# MAIN.net
KiCad netlist of a schematic drawn in Altium Designer
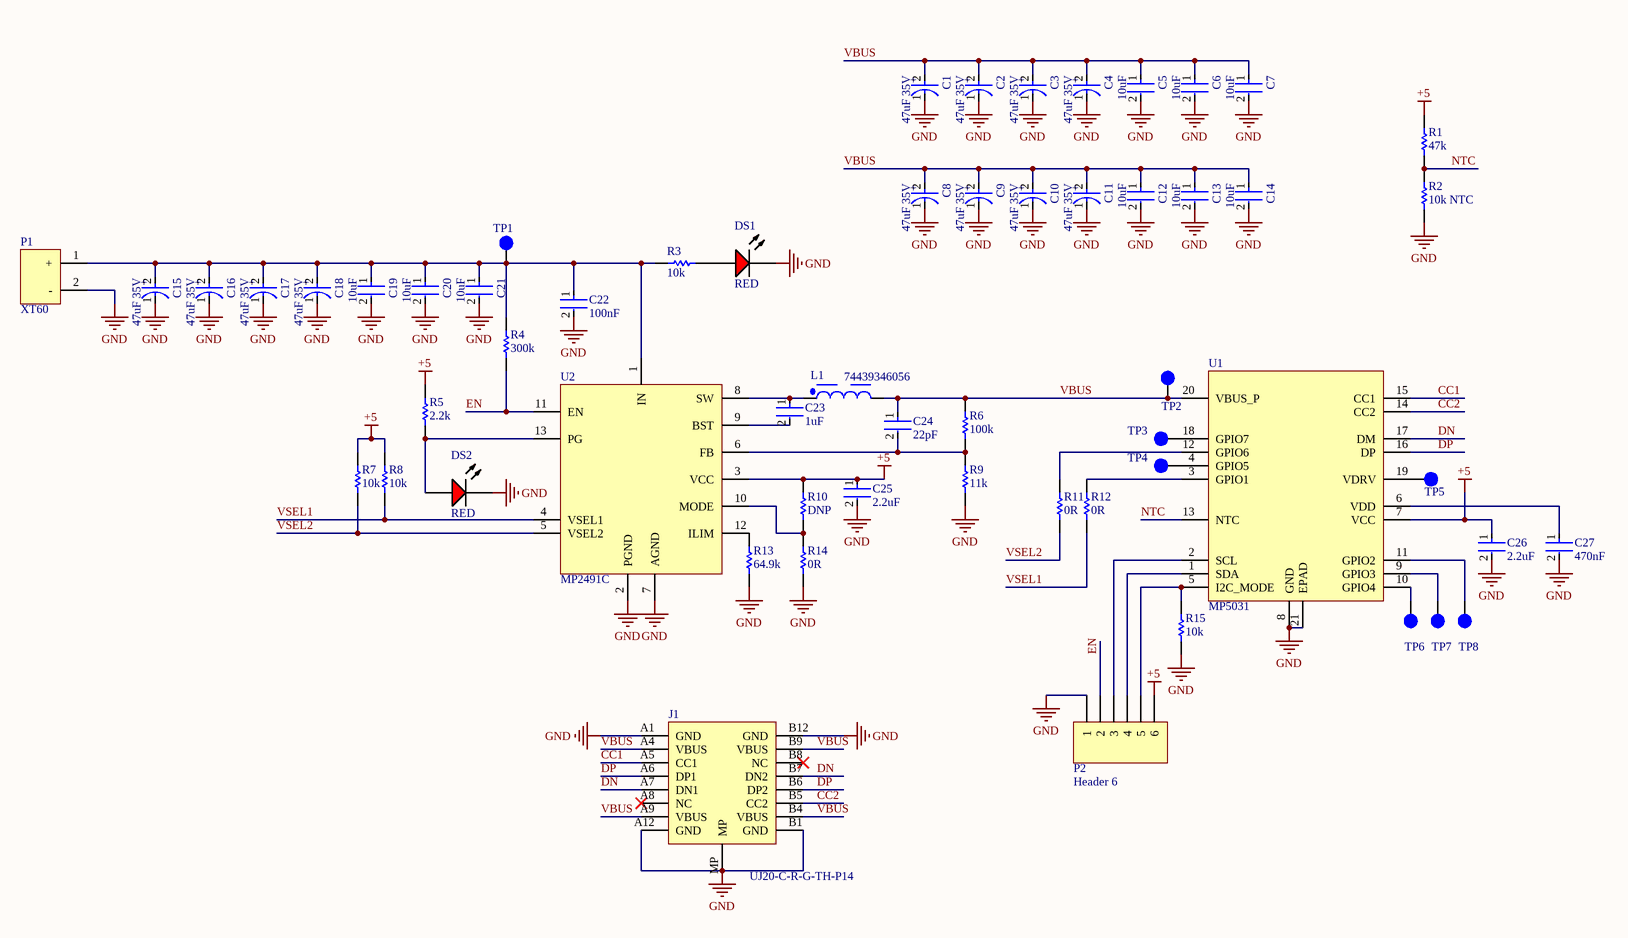
[diagram p0: MAIN.SchDoc]

(export (version "E")
  (design (tool "Eeschema 10.0.6"))
  (components
    (comp (ref "C1")
      (value "47uF 35V")
      (footprint "FP-T491X476K035AT-MFG")
      (description "CAP TANT 47UF 10% 35V 2917")
      (fields (field (name "TOLERANCE") "10%") (field (name "VOLTAGE") "35V"))
      (libsource (lib "Altium Content Vault") (part "203bc49f2ac43e59fd269a8c329ed05"))
    )
    (comp (ref "C2")
      (value "47uF 35V")
      (footprint "FP-T491X476K035AT-MFG")
      (description "CAP TANT 47UF 10% 35V 2917")
      (fields (field (name "TOLERANCE") "10%") (field (name "VOLTAGE") "35V"))
      (libsource (lib "Altium Content Vault") (part "203bc49f2ac43e59fd269a8c329ed05"))
    )
    (comp (ref "C3")
      (value "47uF 35V")
      (footprint "FP-T491X476K035AT-MFG")
      (description "CAP TANT 47UF 10% 35V 2917")
      (fields (field (name "TOLERANCE") "10%") (field (name "VOLTAGE") "35V"))
      (libsource (lib "Altium Content Vault") (part "203bc49f2ac43e59fd269a8c329ed05"))
    )
    (comp (ref "C4")
      (value "47uF 35V")
      (footprint "FP-T491X476K035AT-MFG")
      (description "CAP TANT 47UF 10% 35V 2917")
      (fields (field (name "TOLERANCE") "10%") (field (name "VOLTAGE") "35V"))
      (libsource (lib "Altium Content Vault") (part "203bc49f2ac43e59fd269a8c329ed05"))
    )
    (comp (ref "C5")
      (value "10uF")
      (footprint "FP-1210-L_3_3_0_4-W_2_5_0-IPC_B")
      (description "General Purpose Ceramic Capacitor, 1210, 10uF, 10%, X5R, 15%, 25V")
      (fields (field (name "VOLTAGE") "25V") (field (name "TOLERANCE") "10%"))
      (libsource (lib "Altium Content Vault") (part "b4654b650e69147ec39a6b967a45e02"))
    )
    (comp (ref "C6")
      (value "10uF")
      (footprint "FP-1210-L_3_3_0_4-W_2_5_0-IPC_B")
      (description "General Purpose Ceramic Capacitor, 1210, 10uF, 10%, X5R, 15%, 25V")
      (fields (field (name "VOLTAGE") "25V") (field (name "TOLERANCE") "10%"))
      (libsource (lib "Altium Content Vault") (part "b4654b650e69147ec39a6b967a45e02"))
    )
    (comp (ref "C7")
      (value "10uF")
      (footprint "FP-1210-L_3_3_0_4-W_2_5_0-IPC_B")
      (description "General Purpose Ceramic Capacitor, 1210, 10uF, 10%, X5R, 15%, 25V")
      (fields (field (name "VOLTAGE") "25V") (field (name "TOLERANCE") "10%"))
      (libsource (lib "Altium Content Vault") (part "b4654b650e69147ec39a6b967a45e02"))
    )
    (comp (ref "C8")
      (value "47uF 35V")
      (footprint "FP-T491X476K035AT-MFG")
      (description "CAP TANT 47UF 10% 35V 2917")
      (fields (field (name "TOLERANCE") "10%") (field (name "VOLTAGE") "35V"))
      (libsource (lib "Altium Content Vault") (part "203bc49f2ac43e59fd269a8c329ed05"))
    )
    (comp (ref "C9")
      (value "47uF 35V")
      (footprint "FP-T491X476K035AT-MFG")
      (description "CAP TANT 47UF 10% 35V 2917")
      (fields (field (name "TOLERANCE") "10%") (field (name "VOLTAGE") "35V"))
      (libsource (lib "Altium Content Vault") (part "203bc49f2ac43e59fd269a8c329ed05"))
    )
    (comp (ref "C10")
      (value "47uF 35V")
      (footprint "FP-T491X476K035AT-MFG")
      (description "CAP TANT 47UF 10% 35V 2917")
      (fields (field (name "TOLERANCE") "10%") (field (name "VOLTAGE") "35V"))
      (libsource (lib "Altium Content Vault") (part "203bc49f2ac43e59fd269a8c329ed05"))
    )
    (comp (ref "C11")
      (value "47uF 35V")
      (footprint "FP-T491X476K035AT-MFG")
      (description "CAP TANT 47UF 10% 35V 2917")
      (fields (field (name "TOLERANCE") "10%") (field (name "VOLTAGE") "35V"))
      (libsource (lib "Altium Content Vault") (part "203bc49f2ac43e59fd269a8c329ed05"))
    )
    (comp (ref "C12")
      (value "10uF")
      (footprint "FP-1210-L_3_3_0_4-W_2_5_0-IPC_B")
      (description "General Purpose Ceramic Capacitor, 1210, 10uF, 10%, X5R, 15%, 25V")
      (fields (field (name "VOLTAGE") "25V") (field (name "TOLERANCE") "10%"))
      (libsource (lib "Altium Content Vault") (part "b4654b650e69147ec39a6b967a45e02"))
    )
    (comp (ref "C13")
      (value "10uF")
      (footprint "FP-1210-L_3_3_0_4-W_2_5_0-IPC_B")
      (description "General Purpose Ceramic Capacitor, 1210, 10uF, 10%, X5R, 15%, 25V")
      (fields (field (name "VOLTAGE") "25V") (field (name "TOLERANCE") "10%"))
      (libsource (lib "Altium Content Vault") (part "b4654b650e69147ec39a6b967a45e02"))
    )
    (comp (ref "C14")
      (value "10uF")
      (footprint "FP-1210-L_3_3_0_4-W_2_5_0-IPC_B")
      (description "General Purpose Ceramic Capacitor, 1210, 10uF, 10%, X5R, 15%, 25V")
      (fields (field (name "VOLTAGE") "25V") (field (name "TOLERANCE") "10%"))
      (libsource (lib "Altium Content Vault") (part "b4654b650e69147ec39a6b967a45e02"))
    )
    (comp (ref "C15")
      (value "47uF 35V")
      (footprint "FP-T491X476K035AT-MFG")
      (description "CAP TANT 47UF 10% 35V 2917")
      (fields (field (name "TOLERANCE") "10%") (field (name "VOLTAGE") "35V"))
      (libsource (lib "Altium Content Vault") (part "203bc49f2ac43e59fd269a8c329ed05"))
    )
    (comp (ref "C16")
      (value "47uF 35V")
      (footprint "FP-T491X476K035AT-MFG")
      (description "CAP TANT 47UF 10% 35V 2917")
      (fields (field (name "TOLERANCE") "10%") (field (name "VOLTAGE") "35V"))
      (libsource (lib "Altium Content Vault") (part "203bc49f2ac43e59fd269a8c329ed05"))
    )
    (comp (ref "C17")
      (value "47uF 35V")
      (footprint "FP-T491X476K035AT-MFG")
      (description "CAP TANT 47UF 10% 35V 2917")
      (fields (field (name "TOLERANCE") "10%") (field (name "VOLTAGE") "35V"))
      (libsource (lib "Altium Content Vault") (part "203bc49f2ac43e59fd269a8c329ed05"))
    )
    (comp (ref "C18")
      (value "47uF 35V")
      (footprint "FP-T491X476K035AT-MFG")
      (description "CAP TANT 47UF 10% 35V 2917")
      (fields (field (name "TOLERANCE") "10%") (field (name "VOLTAGE") "35V"))
      (libsource (lib "Altium Content Vault") (part "203bc49f2ac43e59fd269a8c329ed05"))
    )
    (comp (ref "C19")
      (value "10uF")
      (footprint "FP-1210-L_3_3_0_4-W_2_5_0-IPC_B")
      (description "General Purpose Ceramic Capacitor, 1210, 10uF, 10%, X5R, 15%, 25V")
      (fields (field (name "VOLTAGE") "25V") (field (name "TOLERANCE") "10%"))
      (libsource (lib "Altium Content Vault") (part "b4654b650e69147ec39a6b967a45e02"))
    )
    (comp (ref "C20")
      (value "10uF")
      (footprint "FP-1210-L_3_3_0_4-W_2_5_0-IPC_B")
      (description "General Purpose Ceramic Capacitor, 1210, 10uF, 10%, X5R, 15%, 25V")
      (fields (field (name "VOLTAGE") "25V") (field (name "TOLERANCE") "10%"))
      (libsource (lib "Altium Content Vault") (part "b4654b650e69147ec39a6b967a45e02"))
    )
    (comp (ref "C21")
      (value "10uF")
      (footprint "FP-1210-L_3_3_0_4-W_2_5_0-IPC_B")
      (description "General Purpose Ceramic Capacitor, 1210, 10uF, 10%, X5R, 15%, 25V")
      (fields (field (name "VOLTAGE") "25V") (field (name "TOLERANCE") "10%"))
      (libsource (lib "Altium Content Vault") (part "b4654b650e69147ec39a6b967a45e02"))
    )
    (comp (ref "C22")
      (value "100nF")
      (footprint "FP-CGA3E-0_3-0_1-IPC_B")
      (description "Cap Ceramic 100nF 50V X7R 10% Pad SMD 0603 +125°C Automotive T/R")
      (fields (field (name "TOLERANCE") "10%") (field (name "VOLTAGE") "50V"))
      (libsource (lib "Altium Content Vault") (part "b4654b650e69147ec39a6b967a45e02"))
    )
    (comp (ref "C23")
      (value "1uF")
      (footprint "FP-0603-L_1_6_0_15-W_0_81-IPC_B")
      (description "General Purpose Ceramic Capacitor, 0603, 1uF, 10%, X5R, 15%, 16V")
      (fields (field (name "VOLTAGE") "16V") (field (name "TOLERANCE") "10%"))
      (libsource (lib "Altium Content Vault") (part "02cd4be3c70576c341d710602a673aa"))
    )
    (comp (ref "C24")
      (value "22pF")
      (footprint "FP-C0603C-CF-IPC_B")
      (description "Cap Ceramic 22pF 50V C0G 5% SMD 0603 125°C Paper T/R")
      (fields (field (name "MANUFACTURER PART NUMBER") "C0603C220J5GACTU") (field (name "TOLERANCE") "0.05"))
      (libsource (lib "Altium Content Vault") (part "b4654b650e69147ec39a6b967a45e02"))
    )
    (comp (ref "C25")
      (value "2.2uF")
      (footprint "FP-GRM188-0_1-e0_2_0_5-IPC_B")
      (description "Chip Multilayer Ceramic Capacitors for General Purpose, 0603, 2.2uF, X7R, 15%, 10%, 10V")
      (fields (field (name "VOLTAGE") "10V") (field (name "TOLERANCE") "10%"))
      (libsource (lib "Altium Content Vault") (part "11868f565c42a9108669ba33697ecf6"))
    )
    (comp (ref "C26")
      (value "2.2uF")
      (footprint "FP-GRM188-0_1-e0_2_0_5-IPC_B")
      (description "Chip Multilayer Ceramic Capacitors for General Purpose, 0603, 2.2uF, X7R, 15%, 10%, 10V")
      (fields (field (name "VOLTAGE") "10V") (field (name "TOLERANCE") "10%"))
      (libsource (lib "Altium Content Vault") (part "11868f565c42a9108669ba33697ecf6"))
    )
    (comp (ref "C27")
      (value "470nF")
      (footprint "FP-C0603C-CF-IPC_B")
      (description "CAP CER 0.47UF 16V X7R 0603")
      (fields (field (name "TOLERANCE") "0.1") (field (name "MANUFACTURER PART NUMBER") "C0603C474K4RACTU"))
      (libsource (lib "Altium Content Vault") (part "b4654b650e69147ec39a6b967a45e02"))
    )
    (comp (ref "DS1")
      (value "RED")
      (footprint "VISH-TLMX1100_V")
      (description "LED, RED, 2.1 V, -40 to 100 degC, 2-Pin SMD (0603), RoHS, Tape and Reel")
      (fields (field (name "TOLERANCE") "5%"))
      (libsource (lib "Altium Content Vault") (part "LED-RED-AK-2"))
    )
    (comp (ref "DS2")
      (value "RED")
      (footprint "VISH-TLMX1100_V")
      (description "LED, RED, 2.1 V, -40 to 100 degC, 2-Pin SMD (0603), RoHS, Tape and Reel")
      (fields (field (name "TOLERANCE") "5%"))
      (libsource (lib "Altium Content Vault") (part "LED-RED-AK-2"))
    )
    (comp (ref "J1")
      (value "UJ20-C-R-G-TH-P14")
      (footprint "UJ20-C-R-G-TH-P14")
      (libsource (lib "MPS") (part "USB C"))
    )
    (comp (ref "L1")
      (value "74439346056")
      (footprint "WE-XHMI_6060_L6.65W6.45H5.8")
      (description "74439346056 Fixed Ind 5.6UH 6.9A 15MOHM SMD")
      (libsource (lib "Altium Content Vault") (part "Inductor - 2"))
    )
    (comp (ref "P1") (value "XT60") (footprint "XT60") (libsource (lib "MPS") (part "XT60")))
    (comp (ref "P2")
      (value "Header 6")
      (footprint "HDR1X6")
      (description "Header, 6-Pin")
      (fields (field (name "PUBLISHER") "Altium Limited"))
      (libsource (lib "Miscellaneous Connectors") (part "Header 6"))
    )
    (comp (ref "R1")
      (value "47k")
      (footprint "RESC1608X55X30NL15T15")
      (description "Chip Resistor, 47 KOhm, +/- 1%, 0.1 W, -55 to 155 degC, 0603 (1608 Metric), RoHS, Tape and Reel")
      (libsource (lib "Altium Content Vault") (part "RES-2"))
    )
    (comp (ref "R2")
      (value "10k NTC")
      (footprint "RESC1608X90X30NL15T20")
      (fields (field (name "PART NUMBER") "ERT-J1VR103J") (field (name "MANUFACTURER") "Panasonic"))
      (libsource (lib "Altium Content Vault") (part "RES"))
    )
    (comp (ref "R3")
      (value "10k")
      (footprint "RESC1609X55X30NL15T15")
      (description "Chip Resistor, 10 KOhm, +/- 1%, 0.1 W, -55 to 155 degC, 0603 (1608 Metric), RoHS, Tape and Reel")
      (fields (field (name "TOLERANCE") "1%") (field (name "MANUFACTURER") "Panasonic"))
      (libsource (lib "Altium Content Vault") (part "RES-2"))
    )
    (comp (ref "R4")
      (value "300k")
      (footprint "RESC1609X50X30NL10T20")
      (fields (field (name "MANUFACTURER") "Vishay Dale") (field (name "PART NUMBER") "CRCW0603300KFKEA"))
      (libsource (lib "Altium Content Vault") (part "RES"))
    )
    (comp (ref "R5")
      (value "2.2k")
      (footprint "RESC1608X50X30NL20T20")
      (fields (field (name "PART NUMBER") "RR0816P-223-B-T5") (field (name "MANUFACTURER") "Susumu"))
      (libsource (lib "Altium Content Vault") (part "RES"))
    )
    (comp (ref "R6")
      (value "100k")
      (footprint "RESC1608X55X30NL15T15")
      (fields (field (name "PART NUMBER") "ERJ-3EKF1003V") (field (name "MANUFACTURER") "Panasonic"))
      (libsource (lib "Altium Content Vault") (part "RES"))
    )
    (comp (ref "R7")
      (value "10k")
      (footprint "RESC1609X55X30NL15T15")
      (description "Chip Resistor, 10 KOhm, +/- 1%, 0.1 W, -55 to 155 degC, 0603 (1608 Metric), RoHS, Tape and Reel")
      (fields (field (name "TOLERANCE") "1%") (field (name "MANUFACTURER") "Panasonic"))
      (libsource (lib "Altium Content Vault") (part "RES-2"))
    )
    (comp (ref "R8")
      (value "10k")
      (footprint "RESC1609X55X30NL15T15")
      (description "Chip Resistor, 10 KOhm, +/- 1%, 0.1 W, -55 to 155 degC, 0603 (1608 Metric), RoHS, Tape and Reel")
      (fields (field (name "TOLERANCE") "1%") (field (name "MANUFACTURER") "Panasonic"))
      (libsource (lib "Altium Content Vault") (part "RES-2"))
    )
    (comp (ref "R9")
      (value "11k")
      (footprint "RESC1609X50X30NL10T20")
      (fields (field (name "PART NUMBER") "CRCW060311K0FKEA") (field (name "MANUFACTURER") "Vishay Dale"))
      (libsource (lib "Altium Content Vault") (part "RES"))
    )
    (comp (ref "R10")
      (value "DNP")
      (footprint "RESC1608X55X25NL10T15")
      (description "Chip Resistor, 0 Ohm, +/- 5%, 0.1 W, -55 to 155 degC, 0603 (1608 Metric), RoHS, Tape and Reel")
      (fields (field (name "TOLERANCE") "5%") (field (name "MANUFACTURER") "Yageo"))
      (libsource (lib "Altium Content Vault") (part "RES-2"))
    )
    (comp (ref "R11")
      (value "0R")
      (footprint "RESC1608X55X25NL10T15")
      (description "Chip Resistor, 0 Ohm, +/- 5%, 0.1 W, -55 to 155 degC, 0603 (1608 Metric), RoHS, Tape and Reel")
      (fields (field (name "TOLERANCE") "5%") (field (name "MANUFACTURER") "Yageo"))
      (libsource (lib "Altium Content Vault") (part "RES-2"))
    )
    (comp (ref "R12")
      (value "0R")
      (footprint "RESC1608X55X25NL10T15")
      (description "Chip Resistor, 0 Ohm, +/- 5%, 0.1 W, -55 to 155 degC, 0603 (1608 Metric), RoHS, Tape and Reel")
      (fields (field (name "TOLERANCE") "5%") (field (name "MANUFACTURER") "Yageo"))
      (libsource (lib "Altium Content Vault") (part "RES-2"))
    )
    (comp (ref "R13")
      (value "64.9k")
      (footprint "RESC1608X55X30NL15T15")
      (fields (field (name "PART NUMBER") "ERJ-3EKF6492V") (field (name "MANUFACTURER") "Panasonic"))
      (libsource (lib "Altium Content Vault") (part "RES"))
    )
    (comp (ref "R14")
      (value "0R")
      (footprint "RESC1608X55X25NL10T15")
      (description "Chip Resistor, 0 Ohm, +/- 5%, 0.1 W, -55 to 155 degC, 0603 (1608 Metric), RoHS, Tape and Reel")
      (fields (field (name "TOLERANCE") "5%") (field (name "MANUFACTURER") "Yageo"))
      (libsource (lib "Altium Content Vault") (part "RES-2"))
    )
    (comp (ref "R15")
      (value "10k")
      (footprint "RESC1609X55X30NL15T15")
      (description "Chip Resistor, 10 KOhm, +/- 1%, 0.1 W, -55 to 155 degC, 0603 (1608 Metric), RoHS, Tape and Reel")
      (fields (field (name "TOLERANCE") "1%") (field (name "MANUFACTURER") "Panasonic"))
      (libsource (lib "Altium Content Vault") (part "RES-2"))
    )
    (comp (ref "TP1")
      (value "TESTPOINT")
      (footprint "TESTPOINT_0.6")
      (libsource (lib "MPS") (part "TESTPOINT"))
    )
    (comp (ref "TP2")
      (value "TESTPOINT")
      (footprint "TESTPOINT_0.6")
      (libsource (lib "MPS") (part "TESTPOINT"))
    )
    (comp (ref "TP3")
      (value "TESTPOINT")
      (footprint "TESTPOINT_0.6")
      (libsource (lib "MPS") (part "TESTPOINT"))
    )
    (comp (ref "TP4")
      (value "TESTPOINT")
      (footprint "TESTPOINT_0.6")
      (libsource (lib "MPS") (part "TESTPOINT"))
    )
    (comp (ref "TP5")
      (value "TESTPOINT")
      (footprint "TESTPOINT_0.6")
      (libsource (lib "MPS") (part "TESTPOINT"))
    )
    (comp (ref "TP6")
      (value "TESTPOINT")
      (footprint "TESTPOINT_0.6")
      (libsource (lib "MPS") (part "TESTPOINT"))
    )
    (comp (ref "TP7")
      (value "TESTPOINT")
      (footprint "TESTPOINT_0.6")
      (libsource (lib "MPS") (part "TESTPOINT"))
    )
    (comp (ref "TP8")
      (value "TESTPOINT")
      (footprint "TESTPOINT_0.6")
      (libsource (lib "MPS") (part "TESTPOINT"))
    )
    (comp (ref "U1") (value "MP5031") (footprint "QFN-20-MP5031") (libsource (lib "MPS") (part "MP5031")))
    (comp (ref "U2") (value "MP2491C") (footprint "QFN-13-MPS2491C") (libsource (lib "MPS") (part "MP2491C")))
  )
  (nets
    (net (code "1") (name "+5") (class "Default")
      (node (ref "C25") (pin "1") (pinfunction "1_1") (pintype "passive"))
      (node (ref "C26") (pin "1") (pinfunction "1_1") (pintype "passive"))
      (node (ref "P2") (pin "6") (pinfunction "6_6") (pintype "passive"))
      (node (ref "R1") (pin "2") (pinfunction "2_2") (pintype "passive"))
      (node (ref "R10") (pin "2") (pinfunction "2_2") (pintype "passive"))
      (node (ref "R5") (pin "2") (pinfunction "2_2") (pintype "passive"))
      (node (ref "R7") (pin "2") (pinfunction "2_2") (pintype "passive"))
      (node (ref "R8") (pin "2") (pinfunction "2_2") (pintype "passive"))
      (node (ref "U1") (pin "7") (pinfunction "VCC_7") (pintype "passive"))
      (node (ref "U2") (pin "3") (pinfunction "VCC_3") (pintype "passive"))
    )
    (net (code "2") (name "/CC1") (class "Default")
      (node (ref "J1") (pin "A5") (pinfunction "CC1_A5") (pintype "passive"))
      (node (ref "U1") (pin "15") (pinfunction "CC1_15") (pintype "passive"))
    )
    (net (code "3") (name "/CC2") (class "Default")
      (node (ref "J1") (pin "B5") (pinfunction "CC2_B5") (pintype "passive"))
      (node (ref "U1") (pin "14") (pinfunction "CC2_14") (pintype "passive"))
    )
    (net (code "4") (name "/DN") (class "Default")
      (node (ref "J1") (pin "A7") (pinfunction "DN1_A7") (pintype "passive"))
      (node (ref "J1") (pin "B7") (pinfunction "DN2_B7") (pintype "passive"))
      (node (ref "U1") (pin "17") (pinfunction "DM_17") (pintype "passive"))
    )
    (net (code "5") (name "/DP") (class "Default")
      (node (ref "J1") (pin "A6") (pinfunction "DP1_A6") (pintype "passive"))
      (node (ref "J1") (pin "B6") (pinfunction "DP2_B6") (pintype "passive"))
      (node (ref "U1") (pin "16") (pinfunction "DP_16") (pintype "passive"))
    )
    (net (code "6") (name "/EN") (class "Default")
      (node (ref "P2") (pin "2") (pinfunction "2_2") (pintype "passive"))
      (node (ref "R4") (pin "1") (pinfunction "1_1") (pintype "passive"))
      (node (ref "U2") (pin "11") (pinfunction "EN_11") (pintype "passive"))
    )
    (net (code "7") (name "/NTC") (class "Default")
      (node (ref "R1") (pin "1") (pinfunction "1_1") (pintype "passive"))
      (node (ref "R2") (pin "2") (pinfunction "2_2") (pintype "passive"))
      (node (ref "U1") (pin "13") (pinfunction "NTC_13") (pintype "passive"))
    )
    (net (code "8") (name "/VBUS") (class "Default")
      (node (ref "C1") (pin "2") (pinfunction "A_2") (pintype "passive"))
      (node (ref "C10") (pin "2") (pinfunction "A_2") (pintype "passive"))
      (node (ref "C11") (pin "2") (pinfunction "A_2") (pintype "passive"))
      (node (ref "C12") (pin "1") (pinfunction "1_1") (pintype "passive"))
      (node (ref "C13") (pin "1") (pinfunction "1_1") (pintype "passive"))
      (node (ref "C14") (pin "1") (pinfunction "1_1") (pintype "passive"))
      (node (ref "C2") (pin "2") (pinfunction "A_2") (pintype "passive"))
      (node (ref "C24") (pin "1") (pinfunction "1_1") (pintype "passive"))
      (node (ref "C3") (pin "2") (pinfunction "A_2") (pintype "passive"))
      (node (ref "C4") (pin "2") (pinfunction "A_2") (pintype "passive"))
      (node (ref "C5") (pin "1") (pinfunction "1_1") (pintype "passive"))
      (node (ref "C6") (pin "1") (pinfunction "1_1") (pintype "passive"))
      (node (ref "C7") (pin "1") (pinfunction "1_1") (pintype "passive"))
      (node (ref "C8") (pin "2") (pinfunction "A_2") (pintype "passive"))
      (node (ref "C9") (pin "2") (pinfunction "A_2") (pintype "passive"))
      (node (ref "J1") (pin "A4") (pinfunction "VBUS_A4") (pintype "passive"))
      (node (ref "J1") (pin "A9") (pinfunction "VBUS_A9") (pintype "passive"))
      (node (ref "J1") (pin "B4") (pinfunction "VBUS_B4") (pintype "passive"))
      (node (ref "J1") (pin "B9") (pinfunction "VBUS_B9") (pintype "passive"))
      (node (ref "L1") (pin "2") (pinfunction "2_2") (pintype "passive"))
      (node (ref "R6") (pin "2") (pinfunction "2_2") (pintype "passive"))
      (node (ref "TP2") (pin "1") (pinfunction "1_1") (pintype "passive"))
      (node (ref "U1") (pin "20") (pinfunction "VBUS_P_20") (pintype "passive"))
    )
    (net (code "9") (name "/VSEL1") (class "Default")
      (node (ref "R12") (pin "1") (pinfunction "1_1") (pintype "passive"))
      (node (ref "R8") (pin "1") (pinfunction "1_1") (pintype "passive"))
      (node (ref "U2") (pin "4") (pinfunction "VSEL1_4") (pintype "passive"))
    )
    (net (code "10") (name "/VSEL2") (class "Default")
      (node (ref "R11") (pin "1") (pinfunction "1_1") (pintype "passive"))
      (node (ref "R7") (pin "1") (pinfunction "1_1") (pintype "passive"))
      (node (ref "U2") (pin "5") (pinfunction "VSEL2_5") (pintype "passive"))
    )
    (net (code "11") (name "GND") (class "Default")
      (node (ref "C1") (pin "1") (pinfunction "C_1") (pintype "passive"))
      (node (ref "C10") (pin "1") (pinfunction "C_1") (pintype "passive"))
      (node (ref "C11") (pin "1") (pinfunction "C_1") (pintype "passive"))
      (node (ref "C12") (pin "2") (pinfunction "2_2") (pintype "passive"))
      (node (ref "C13") (pin "2") (pinfunction "2_2") (pintype "passive"))
      (node (ref "C14") (pin "2") (pinfunction "2_2") (pintype "passive"))
      (node (ref "C15") (pin "1") (pinfunction "C_1") (pintype "passive"))
      (node (ref "C16") (pin "1") (pinfunction "C_1") (pintype "passive"))
      (node (ref "C17") (pin "1") (pinfunction "C_1") (pintype "passive"))
      (node (ref "C18") (pin "1") (pinfunction "C_1") (pintype "passive"))
      (node (ref "C19") (pin "2") (pinfunction "2_2") (pintype "passive"))
      (node (ref "C2") (pin "1") (pinfunction "C_1") (pintype "passive"))
      (node (ref "C20") (pin "2") (pinfunction "2_2") (pintype "passive"))
      (node (ref "C21") (pin "2") (pinfunction "2_2") (pintype "passive"))
      (node (ref "C22") (pin "2") (pinfunction "2_2") (pintype "passive"))
      (node (ref "C25") (pin "2") (pinfunction "2_2") (pintype "passive"))
      (node (ref "C26") (pin "2") (pinfunction "2_2") (pintype "passive"))
      (node (ref "C27") (pin "2") (pinfunction "2_2") (pintype "passive"))
      (node (ref "C3") (pin "1") (pinfunction "C_1") (pintype "passive"))
      (node (ref "C4") (pin "1") (pinfunction "C_1") (pintype "passive"))
      (node (ref "C5") (pin "2") (pinfunction "2_2") (pintype "passive"))
      (node (ref "C6") (pin "2") (pinfunction "2_2") (pintype "passive"))
      (node (ref "C7") (pin "2") (pinfunction "2_2") (pintype "passive"))
      (node (ref "C8") (pin "1") (pinfunction "C_1") (pintype "passive"))
      (node (ref "C9") (pin "1") (pinfunction "C_1") (pintype "passive"))
      (node (ref "DS1") (pin "2") (pinfunction "K_2") (pintype "passive"))
      (node (ref "DS2") (pin "2") (pinfunction "K_2") (pintype "passive"))
      (node (ref "J1") (pin "A1") (pinfunction "GND_A1") (pintype "passive"))
      (node (ref "J1") (pin "A12") (pinfunction "GND_A12") (pintype "passive"))
      (node (ref "J1") (pin "B1") (pinfunction "GND_B1") (pintype "passive"))
      (node (ref "J1") (pin "B12") (pinfunction "GND_B12") (pintype "passive"))
      (node (ref "J1") (pin "MP") (pinfunction "MP_MP") (pintype "passive"))
      (node (ref "P1") (pin "2") (pinfunction "-_2") (pintype "passive"))
      (node (ref "P2") (pin "1") (pinfunction "1_1") (pintype "passive"))
      (node (ref "R13") (pin "1") (pinfunction "1_1") (pintype "passive"))
      (node (ref "R14") (pin "1") (pinfunction "1_1") (pintype "passive"))
      (node (ref "R15") (pin "1") (pinfunction "1_1") (pintype "passive"))
      (node (ref "R2") (pin "1") (pinfunction "1_1") (pintype "passive"))
      (node (ref "R9") (pin "1") (pinfunction "1_1") (pintype "passive"))
      (node (ref "U1") (pin "21") (pinfunction "EPAD_21") (pintype "passive"))
      (node (ref "U1") (pin "8") (pinfunction "GND_8") (pintype "passive"))
      (node (ref "U2") (pin "2") (pinfunction "PGND_2") (pintype "passive"))
      (node (ref "U2") (pin "7") (pinfunction "AGND_7") (pintype "passive"))
    )
    (net (code "12") (name "Net-(C15-A)") (class "Default")
      (node (ref "C15") (pin "2") (pinfunction "A_2") (pintype "passive"))
      (node (ref "C16") (pin "2") (pinfunction "A_2") (pintype "passive"))
      (node (ref "C17") (pin "2") (pinfunction "A_2") (pintype "passive"))
      (node (ref "C18") (pin "2") (pinfunction "A_2") (pintype "passive"))
      (node (ref "C19") (pin "1") (pinfunction "1_1") (pintype "passive"))
      (node (ref "C20") (pin "1") (pinfunction "1_1") (pintype "passive"))
      (node (ref "C21") (pin "1") (pinfunction "1_1") (pintype "passive"))
      (node (ref "C22") (pin "1") (pinfunction "1_1") (pintype "passive"))
      (node (ref "P1") (pin "1") (pinfunction "+_1") (pintype "passive"))
      (node (ref "R3") (pin "2") (pinfunction "2_2") (pintype "passive"))
      (node (ref "R4") (pin "2") (pinfunction "2_2") (pintype "passive"))
      (node (ref "TP1") (pin "1") (pinfunction "1_1") (pintype "passive"))
      (node (ref "U2") (pin "1") (pinfunction "IN_1") (pintype "passive"))
    )
    (net (code "13") (name "Net-(DS1-A)") (class "Default")
      (node (ref "DS1") (pin "1") (pinfunction "A_1") (pintype "passive"))
      (node (ref "R3") (pin "1") (pinfunction "1_1") (pintype "passive"))
    )
    (net (code "14") (name "Net-(DS2-A)") (class "Default")
      (node (ref "DS2") (pin "1") (pinfunction "A_1") (pintype "passive"))
      (node (ref "R5") (pin "1") (pinfunction "1_1") (pintype "passive"))
      (node (ref "U2") (pin "13") (pinfunction "PG_13") (pintype "passive"))
    )
    (net (code "15") (name "Net-(U1-GPIO1)") (class "Default")
      (node (ref "R12") (pin "2") (pinfunction "2_2") (pintype "passive"))
      (node (ref "U1") (pin "3") (pinfunction "GPIO1_3") (pintype "passive"))
    )
    (net (code "16") (name "Net-(U1-GPIO2)") (class "Default")
      (node (ref "TP8") (pin "1") (pinfunction "1_1") (pintype "passive"))
      (node (ref "U1") (pin "11") (pinfunction "GPIO2_11") (pintype "passive"))
    )
    (net (code "17") (name "Net-(U1-GPIO3)") (class "Default")
      (node (ref "TP7") (pin "1") (pinfunction "1_1") (pintype "passive"))
      (node (ref "U1") (pin "9") (pinfunction "GPIO3_9") (pintype "passive"))
    )
    (net (code "18") (name "Net-(U1-GPIO4)") (class "Default")
      (node (ref "TP6") (pin "1") (pinfunction "1_1") (pintype "passive"))
      (node (ref "U1") (pin "10") (pinfunction "GPIO4_10") (pintype "passive"))
    )
    (net (code "19") (name "Net-(U1-GPIO5)") (class "Default")
      (node (ref "TP4") (pin "1") (pinfunction "1_1") (pintype "passive"))
      (node (ref "U1") (pin "4") (pinfunction "GPIO5_4") (pintype "passive"))
    )
    (net (code "20") (name "Net-(U1-GPIO6)") (class "Default")
      (node (ref "R11") (pin "2") (pinfunction "2_2") (pintype "passive"))
      (node (ref "U1") (pin "12") (pinfunction "GPIO6_12") (pintype "passive"))
    )
    (net (code "21") (name "Net-(U1-GPIO7)") (class "Default")
      (node (ref "TP3") (pin "1") (pinfunction "1_1") (pintype "passive"))
      (node (ref "U1") (pin "18") (pinfunction "GPIO7_18") (pintype "passive"))
    )
    (net (code "22") (name "Net-(U1-I2C_MODE)") (class "Default")
      (node (ref "P2") (pin "5") (pinfunction "5_5") (pintype "passive"))
      (node (ref "R15") (pin "2") (pinfunction "2_2") (pintype "passive"))
      (node (ref "U1") (pin "5") (pinfunction "I2C_MODE_5") (pintype "passive"))
    )
    (net (code "23") (name "Net-(U1-SCL)") (class "Default")
      (node (ref "P2") (pin "3") (pinfunction "3_3") (pintype "passive"))
      (node (ref "U1") (pin "2") (pinfunction "SCL_2") (pintype "passive"))
    )
    (net (code "24") (name "Net-(U1-SDA)") (class "Default")
      (node (ref "P2") (pin "4") (pinfunction "4_4") (pintype "passive"))
      (node (ref "U1") (pin "1") (pinfunction "SDA_1") (pintype "passive"))
    )
    (net (code "25") (name "Net-(U1-VDD)") (class "Default")
      (node (ref "C27") (pin "1") (pinfunction "1_1") (pintype "passive"))
      (node (ref "U1") (pin "6") (pinfunction "VDD_6") (pintype "passive"))
    )
    (net (code "26") (name "Net-(U1-VDRV)") (class "Default")
      (node (ref "TP5") (pin "1") (pinfunction "1_1") (pintype "passive"))
      (node (ref "U1") (pin "19") (pinfunction "VDRV_19") (pintype "passive"))
    )
    (net (code "27") (name "Net-(U2-BST)") (class "Default")
      (node (ref "C23") (pin "2") (pinfunction "2_2") (pintype "passive"))
      (node (ref "U2") (pin "9") (pinfunction "BST_9") (pintype "passive"))
    )
    (net (code "28") (name "Net-(U2-FB)") (class "Default")
      (node (ref "C24") (pin "2") (pinfunction "2_2") (pintype "passive"))
      (node (ref "R6") (pin "1") (pinfunction "1_1") (pintype "passive"))
      (node (ref "R9") (pin "2") (pinfunction "2_2") (pintype "passive"))
      (node (ref "U2") (pin "6") (pinfunction "FB_6") (pintype "passive"))
    )
    (net (code "29") (name "Net-(U2-ILIM)") (class "Default")
      (node (ref "R13") (pin "2") (pinfunction "2_2") (pintype "passive"))
      (node (ref "U2") (pin "12") (pinfunction "ILIM_12") (pintype "passive"))
    )
    (net (code "30") (name "Net-(U2-MODE)") (class "Default")
      (node (ref "R10") (pin "1") (pinfunction "1_1") (pintype "passive"))
      (node (ref "R14") (pin "2") (pinfunction "2_2") (pintype "passive"))
      (node (ref "U2") (pin "10") (pinfunction "MODE_10") (pintype "passive"))
    )
    (net (code "31") (name "Net-(U2-SW)") (class "Default")
      (node (ref "C23") (pin "1") (pinfunction "1_1") (pintype "passive"))
      (node (ref "L1") (pin "1") (pinfunction "1_1") (pintype "passive"))
      (node (ref "U2") (pin "8") (pinfunction "SW_8") (pintype "passive"))
    )
    (net (code "32") (name "unconnected-(J1-NC-PadA8)") (class "Default")
      (node (ref "J1") (pin "A8") (pinfunction "NC_A8") (pintype "passive+no_connect"))
    )
    (net (code "33") (name "unconnected-(J1-NC-PadB8)") (class "Default")
      (node (ref "J1") (pin "B8") (pinfunction "NC_B8") (pintype "passive+no_connect"))
    )
  )
)
